# KUBODriver_Driver.net
KiCad netlist of a schematic drawn in Altium Designer
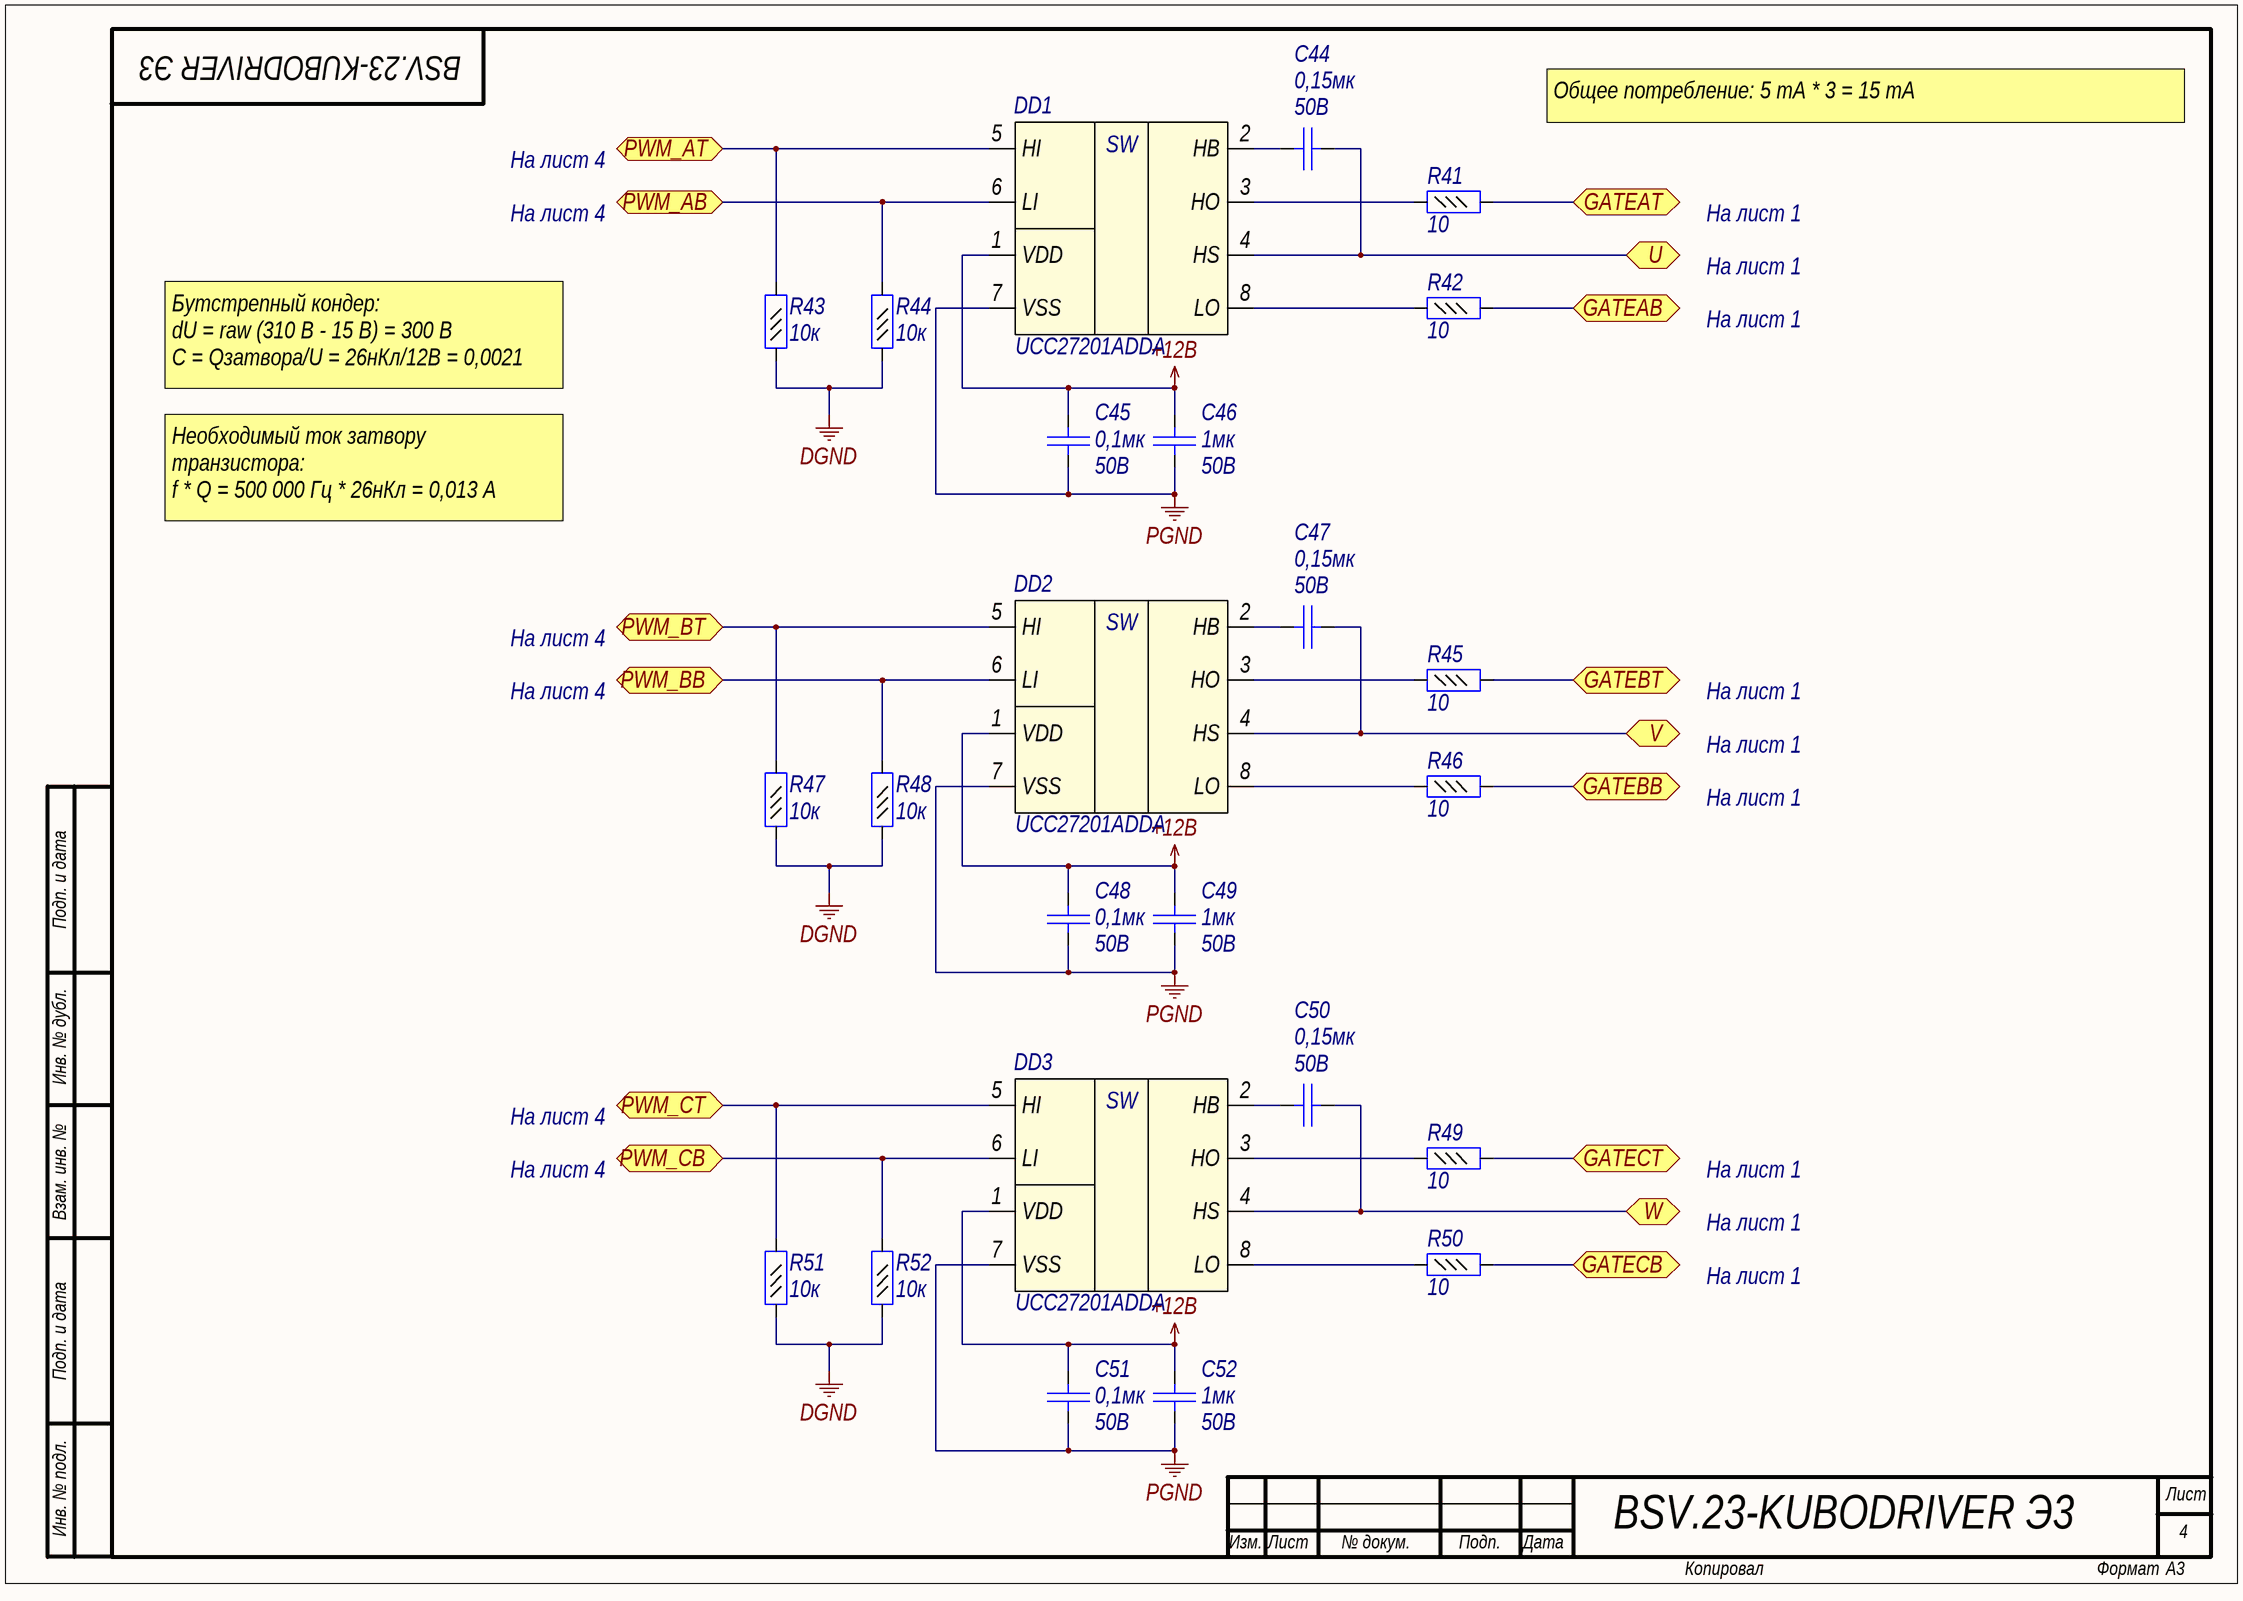
[diagram p0: KUBODriver_Driver.SchDoc]

(export (version "E")
  (design (tool "Eeschema 10.0.6"))
  (components
    (comp (ref "C44")
      (value "0,15мк")
      (footprint "C1812")
      (description "Конденсатор")
      (fields (field (name "VOLTAGE") "50В") (field (name "PART NUMBER") "C4532C0G1H154J250KA "))
      (libsource (lib "MOP44") (part "Capacitor"))
    )
    (comp (ref "C45")
      (value "0,1мк")
      (footprint "C0402")
      (description "Конденсатор")
      (fields
        (field (name "VOLTAGE") "50В")
        (field (name "PART NUMBER") "GRM155R71H104KE14D ")
        (field (name "Comment") "Capacitor")
      )
      (libsource (lib "MOP44") (part "Capacitor"))
    )
    (comp (ref "C46")
      (value "1мк")
      (footprint "C0805")
      (description "Конденсатор")
      (fields
        (field (name "VOLTAGE") "50B")
        (field (name "PART NUMBER") "GRM21BR71H105K")
        (field (name "Comment") "Capacitor")
      )
      (libsource (lib "MOP44") (part "Capacitor"))
    )
    (comp (ref "C47")
      (value "0,15мк")
      (footprint "C1812")
      (description "Конденсатор")
      (fields (field (name "VOLTAGE") "50В") (field (name "PART NUMBER") "C4532C0G1H154J250KA "))
      (libsource (lib "MOP44") (part "Capacitor"))
    )
    (comp (ref "C48")
      (value "0,1мк")
      (footprint "C0402")
      (description "Конденсатор")
      (fields
        (field (name "VOLTAGE") "50В")
        (field (name "PART NUMBER") "GRM155R71H104KE14D ")
        (field (name "Comment") "Capacitor")
      )
      (libsource (lib "MOP44") (part "Capacitor"))
    )
    (comp (ref "C49")
      (value "1мк")
      (footprint "C0805")
      (description "Конденсатор")
      (fields
        (field (name "VOLTAGE") "50B")
        (field (name "PART NUMBER") "GRM21BR71H105K")
        (field (name "Comment") "Capacitor")
      )
      (libsource (lib "MOP44") (part "Capacitor"))
    )
    (comp (ref "C50")
      (value "0,15мк")
      (footprint "C1812")
      (description "Конденсатор")
      (fields (field (name "VOLTAGE") "50В") (field (name "PART NUMBER") "C4532C0G1H154J250KA "))
      (libsource (lib "MOP44") (part "Capacitor"))
    )
    (comp (ref "C51")
      (value "0,1мк")
      (footprint "C0402")
      (description "Конденсатор")
      (fields
        (field (name "VOLTAGE") "50В")
        (field (name "PART NUMBER") "GRM155R71H104KE14D ")
        (field (name "Comment") "Capacitor")
      )
      (libsource (lib "MOP44") (part "Capacitor"))
    )
    (comp (ref "C52")
      (value "1мк")
      (footprint "C0805")
      (description "Конденсатор")
      (fields
        (field (name "VOLTAGE") "50B")
        (field (name "PART NUMBER") "GRM21BR71H105K")
        (field (name "Comment") "Capacitor")
      )
      (libsource (lib "MOP44") (part "Capacitor"))
    )
    (comp (ref "DD1")
      (value "UCC27201A")
      (footprint "HSOP8")
      (description "120-V Boot, 3-A Peak, High-Frequency, High-Side and Low-Side Driver")
      (fields (field (name "PART NUMBER") "UCC27201ADDA"))
      (libsource (lib "MOP44") (part "UCC27201A"))
    )
    (comp (ref "DD2")
      (value "UCC27201A")
      (footprint "HSOP8")
      (description "120-V Boot, 3-A Peak, High-Frequency, High-Side and Low-Side Driver")
      (fields (field (name "PART NUMBER") "UCC27201ADDA"))
      (libsource (lib "MOP44") (part "UCC27201A"))
    )
    (comp (ref "DD3")
      (value "UCC27201A")
      (footprint "HSOP8")
      (description "120-V Boot, 3-A Peak, High-Frequency, High-Side and Low-Side Driver")
      (fields (field (name "PART NUMBER") "UCC27201ADDA"))
      (libsource (lib "MOP44") (part "UCC27201A"))
    )
    (comp (ref "R41")
      (value "10")
      (footprint "R0402")
      (description "Резистор")
      (fields (field (name "PART NUMBER") "RC0402FR-0710RL") (field (name "POWER") "0,062Вт"))
      (libsource (lib "MOP44") (part "Resistor_0,062Вт"))
    )
    (comp (ref "R42")
      (value "10")
      (footprint "R0402")
      (description "Резистор")
      (fields (field (name "PART NUMBER") "RC0402FR-0710RL") (field (name "POWER") "0,062Вт"))
      (libsource (lib "MOP44") (part "Resistor_0,062Вт"))
    )
    (comp (ref "R43")
      (value "10к")
      (footprint "R0402")
      (description "Резистор")
      (fields (field (name "PART NUMBER") "RC0402FR-0710KL") (field (name "POWER") "0,062Вт"))
      (libsource (lib "") (part "Resistor_0,062Вт_1"))
    )
    (comp (ref "R44")
      (value "10к")
      (footprint "R0402")
      (description "Резистор")
      (fields (field (name "PART NUMBER") "RC0402FR-0710KL") (field (name "POWER") "0,062Вт"))
      (libsource (lib "") (part "Resistor_0,062Вт_1"))
    )
    (comp (ref "R45")
      (value "10")
      (footprint "R0402")
      (description "Резистор")
      (fields (field (name "PART NUMBER") "RC0402FR-0710RL") (field (name "POWER") "0,062Вт"))
      (libsource (lib "MOP44") (part "Resistor_0,062Вт"))
    )
    (comp (ref "R46")
      (value "10")
      (footprint "R0402")
      (description "Резистор")
      (fields (field (name "PART NUMBER") "RC0402FR-0710RL") (field (name "POWER") "0,062Вт"))
      (libsource (lib "MOP44") (part "Resistor_0,062Вт"))
    )
    (comp (ref "R47")
      (value "10к")
      (footprint "R0402")
      (description "Резистор")
      (fields (field (name "PART NUMBER") "RC0402FR-0710KL") (field (name "POWER") "0,062Вт"))
      (libsource (lib "") (part "Resistor_0,062Вт_1"))
    )
    (comp (ref "R48")
      (value "10к")
      (footprint "R0402")
      (description "Резистор")
      (fields (field (name "PART NUMBER") "RC0402FR-0710KL") (field (name "POWER") "0,062Вт"))
      (libsource (lib "") (part "Resistor_0,062Вт_1"))
    )
    (comp (ref "R49")
      (value "10")
      (footprint "R0402")
      (description "Резистор")
      (fields (field (name "PART NUMBER") "RC0402FR-0710RL") (field (name "POWER") "0,062Вт"))
      (libsource (lib "MOP44") (part "Resistor_0,062Вт"))
    )
    (comp (ref "R50")
      (value "10")
      (footprint "R0402")
      (description "Резистор")
      (fields (field (name "PART NUMBER") "RC0402FR-0710RL") (field (name "POWER") "0,062Вт"))
      (libsource (lib "MOP44") (part "Resistor_0,062Вт"))
    )
    (comp (ref "R51")
      (value "10к")
      (footprint "R0402")
      (description "Резистор")
      (fields (field (name "PART NUMBER") "RC0402FR-0710KL") (field (name "POWER") "0,062Вт"))
      (libsource (lib "") (part "Resistor_0,062Вт_1"))
    )
    (comp (ref "R52")
      (value "10к")
      (footprint "R0402")
      (description "Резистор")
      (fields (field (name "PART NUMBER") "RC0402FR-0710KL") (field (name "POWER") "0,062Вт"))
      (libsource (lib "") (part "Resistor_0,062Вт_1"))
    )
  )
  (nets
    (net (code "1") (name "+12B") (class "Default")
      (node (ref "C45") (pin "2") (pinfunction "2_2") (pintype "passive"))
      (node (ref "C46") (pin "2") (pinfunction "2_2") (pintype "passive"))
      (node (ref "C48") (pin "2") (pinfunction "2_2") (pintype "passive"))
      (node (ref "C49") (pin "2") (pinfunction "2_2") (pintype "passive"))
      (node (ref "C51") (pin "2") (pinfunction "2_2") (pintype "passive"))
      (node (ref "C52") (pin "2") (pinfunction "2_2") (pintype "passive"))
      (node (ref "DD1") (pin "1") (pinfunction "VDD_1") (pintype "passive"))
      (node (ref "DD2") (pin "1") (pinfunction "VDD_1") (pintype "passive"))
      (node (ref "DD3") (pin "1") (pinfunction "VDD_1") (pintype "passive"))
    )
    (net (code "2") (name "/GATEAB") (class "Default")
      (node (ref "R42") (pin "2") (pinfunction "2_2") (pintype "passive"))
    )
    (net (code "3") (name "/GATEAT") (class "Default")
      (node (ref "R41") (pin "2") (pinfunction "2_2") (pintype "passive"))
    )
    (net (code "4") (name "/GATEBB") (class "Default")
      (node (ref "R46") (pin "2") (pinfunction "2_2") (pintype "passive"))
    )
    (net (code "5") (name "/GATEBT") (class "Default")
      (node (ref "R45") (pin "2") (pinfunction "2_2") (pintype "passive"))
    )
    (net (code "6") (name "/GATECB") (class "Default")
      (node (ref "R50") (pin "2") (pinfunction "2_2") (pintype "passive"))
    )
    (net (code "7") (name "/GATECT") (class "Default")
      (node (ref "R49") (pin "2") (pinfunction "2_2") (pintype "passive"))
    )
    (net (code "8") (name "/PWM_AB") (class "Default")
      (node (ref "DD1") (pin "6") (pinfunction "LI_6") (pintype "passive"))
      (node (ref "R44") (pin "2") (pinfunction "2_2") (pintype "passive"))
    )
    (net (code "9") (name "/PWM_AT") (class "Default")
      (node (ref "DD1") (pin "5") (pinfunction "HI_5") (pintype "passive"))
      (node (ref "R43") (pin "2") (pinfunction "2_2") (pintype "passive"))
    )
    (net (code "10") (name "/PWM_BB") (class "Default")
      (node (ref "DD2") (pin "6") (pinfunction "LI_6") (pintype "passive"))
      (node (ref "R48") (pin "2") (pinfunction "2_2") (pintype "passive"))
    )
    (net (code "11") (name "/PWM_BT") (class "Default")
      (node (ref "DD2") (pin "5") (pinfunction "HI_5") (pintype "passive"))
      (node (ref "R47") (pin "2") (pinfunction "2_2") (pintype "passive"))
    )
    (net (code "12") (name "/PWM_CB") (class "Default")
      (node (ref "DD3") (pin "6") (pinfunction "LI_6") (pintype "passive"))
      (node (ref "R52") (pin "2") (pinfunction "2_2") (pintype "passive"))
    )
    (net (code "13") (name "/PWM_CT") (class "Default")
      (node (ref "DD3") (pin "5") (pinfunction "HI_5") (pintype "passive"))
      (node (ref "R51") (pin "2") (pinfunction "2_2") (pintype "passive"))
    )
    (net (code "14") (name "/U") (class "Default")
      (node (ref "C44") (pin "2") (pinfunction "2_2") (pintype "passive"))
      (node (ref "DD1") (pin "4") (pinfunction "HS_4") (pintype "passive"))
    )
    (net (code "15") (name "/V") (class "Default")
      (node (ref "C47") (pin "2") (pinfunction "2_2") (pintype "passive"))
      (node (ref "DD2") (pin "4") (pinfunction "HS_4") (pintype "passive"))
    )
    (net (code "16") (name "/W") (class "Default")
      (node (ref "C50") (pin "2") (pinfunction "2_2") (pintype "passive"))
      (node (ref "DD3") (pin "4") (pinfunction "HS_4") (pintype "passive"))
    )
    (net (code "17") (name "DGND") (class "Default")
      (node (ref "R43") (pin "1") (pinfunction "1_1") (pintype "passive"))
      (node (ref "R44") (pin "1") (pinfunction "1_1") (pintype "passive"))
      (node (ref "R47") (pin "1") (pinfunction "1_1") (pintype "passive"))
      (node (ref "R48") (pin "1") (pinfunction "1_1") (pintype "passive"))
      (node (ref "R51") (pin "1") (pinfunction "1_1") (pintype "passive"))
      (node (ref "R52") (pin "1") (pinfunction "1_1") (pintype "passive"))
    )
    (net (code "18") (name "Net-(DD1-HB)") (class "Default")
      (node (ref "C44") (pin "1") (pinfunction "1_1") (pintype "passive"))
      (node (ref "DD1") (pin "2") (pinfunction "HB_2") (pintype "passive"))
    )
    (net (code "19") (name "Net-(DD1-HO)") (class "Default")
      (node (ref "DD1") (pin "3") (pinfunction "HO_3") (pintype "passive"))
      (node (ref "R41") (pin "1") (pinfunction "1_1") (pintype "passive"))
    )
    (net (code "20") (name "Net-(DD1-LO)") (class "Default")
      (node (ref "DD1") (pin "8") (pinfunction "LO_8") (pintype "passive"))
      (node (ref "R42") (pin "1") (pinfunction "1_1") (pintype "passive"))
    )
    (net (code "21") (name "Net-(DD2-HB)") (class "Default")
      (node (ref "C47") (pin "1") (pinfunction "1_1") (pintype "passive"))
      (node (ref "DD2") (pin "2") (pinfunction "HB_2") (pintype "passive"))
    )
    (net (code "22") (name "Net-(DD2-HO)") (class "Default")
      (node (ref "DD2") (pin "3") (pinfunction "HO_3") (pintype "passive"))
      (node (ref "R45") (pin "1") (pinfunction "1_1") (pintype "passive"))
    )
    (net (code "23") (name "Net-(DD2-LO)") (class "Default")
      (node (ref "DD2") (pin "8") (pinfunction "LO_8") (pintype "passive"))
      (node (ref "R46") (pin "1") (pinfunction "1_1") (pintype "passive"))
    )
    (net (code "24") (name "Net-(DD3-HB)") (class "Default")
      (node (ref "C50") (pin "1") (pinfunction "1_1") (pintype "passive"))
      (node (ref "DD3") (pin "2") (pinfunction "HB_2") (pintype "passive"))
    )
    (net (code "25") (name "Net-(DD3-HO)") (class "Default")
      (node (ref "DD3") (pin "3") (pinfunction "HO_3") (pintype "passive"))
      (node (ref "R49") (pin "1") (pinfunction "1_1") (pintype "passive"))
    )
    (net (code "26") (name "Net-(DD3-LO)") (class "Default")
      (node (ref "DD3") (pin "8") (pinfunction "LO_8") (pintype "passive"))
      (node (ref "R50") (pin "1") (pinfunction "1_1") (pintype "passive"))
    )
    (net (code "27") (name "PGND") (class "Default")
      (node (ref "C45") (pin "1") (pinfunction "1_1") (pintype "passive"))
      (node (ref "C46") (pin "1") (pinfunction "1_1") (pintype "passive"))
      (node (ref "C48") (pin "1") (pinfunction "1_1") (pintype "passive"))
      (node (ref "C49") (pin "1") (pinfunction "1_1") (pintype "passive"))
      (node (ref "C51") (pin "1") (pinfunction "1_1") (pintype "passive"))
      (node (ref "C52") (pin "1") (pinfunction "1_1") (pintype "passive"))
      (node (ref "DD1") (pin "7") (pinfunction "VSS_7") (pintype "passive"))
      (node (ref "DD2") (pin "7") (pinfunction "VSS_7") (pintype "passive"))
      (node (ref "DD3") (pin "7") (pinfunction "VSS_7") (pintype "passive"))
    )
  )
)
